# Schematic.net
KiCad netlist of a schematic drawn in Altium Designer
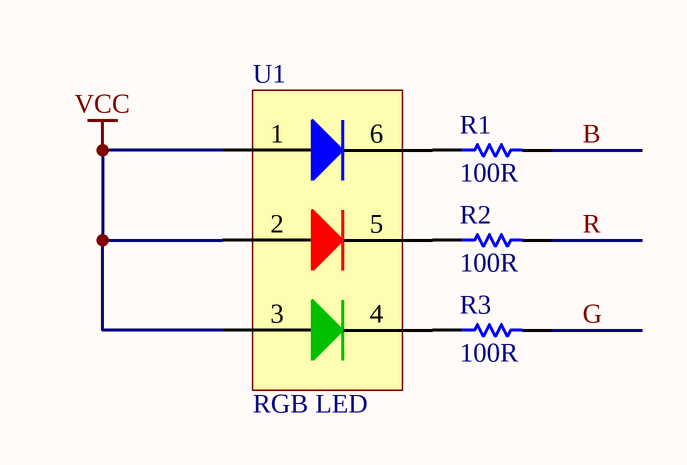
[diagram p0: Schematic.SchDoc]

(export (version "E")
  (design (tool "Eeschema 10.0.6"))
  (components
    (comp (ref "R1")
      (value "100R")
      (footprint "1206")
      (description "Resistor")
      (fields (field (name "Comment") "Res1") (field (name "PUBLISHER") "Altium Limited"))
      (libsource (lib "Miscellaneous Devices") (part "Res1"))
    )
    (comp (ref "R2")
      (value "100R")
      (footprint "1206")
      (description "Resistor")
      (fields (field (name "Comment") "Res1") (field (name "PUBLISHER") "Altium Limited"))
      (libsource (lib "Miscellaneous Devices") (part "Res1"))
    )
    (comp (ref "R3")
      (value "100R")
      (footprint "1206")
      (description "Resistor")
      (fields (field (name "Comment") "Res1") (field (name "PUBLISHER") "Altium Limited"))
      (libsource (lib "Miscellaneous Devices") (part "Res1"))
    )
    (comp (ref "U1")
      (value "RGB LED")
      (footprint "6pin_0604")
      (libsource (lib "MySchLib") (part "SMLP36RGB2W3"))
    )
  )
  (nets
    (net (code "1") (name "/B") (class "Default")
      (node (ref "R1") (pin "2") (pinfunction "2_2") (pintype "passive"))
    )
    (net (code "2") (name "/G") (class "Default")
      (node (ref "R3") (pin "2") (pinfunction "2_2") (pintype "passive"))
    )
    (net (code "3") (name "/R") (class "Default")
      (node (ref "R2") (pin "2") (pinfunction "2_2") (pintype "passive"))
    )
    (net (code "4") (name "Net-(R2-Pad1)") (class "Default")
      (node (ref "R2") (pin "1") (pinfunction "1_1") (pintype "passive"))
      (node (ref "U1") (pin "5") (pinfunction "Rcathod_5") (pintype "passive"))
    )
    (net (code "5") (name "Net-(R3-Pad1)") (class "Default")
      (node (ref "R3") (pin "1") (pinfunction "1_1") (pintype "passive"))
      (node (ref "U1") (pin "4") (pinfunction "Rcathod_4") (pintype "passive"))
    )
    (net (code "6") (name "Net-(U1-Bcathod)") (class "Default")
      (node (ref "R1") (pin "1") (pinfunction "1_1") (pintype "passive"))
      (node (ref "U1") (pin "6") (pinfunction "Bcathod_6") (pintype "passive"))
    )
    (net (code "7") (name "VCC") (class "Default")
      (node (ref "U1") (pin "1") (pinfunction "Banode_1") (pintype "passive"))
      (node (ref "U1") (pin "2") (pinfunction "Ranode_2") (pintype "passive"))
      (node (ref "U1") (pin "3") (pinfunction "Ranode_3") (pintype "passive"))
    )
  )
)
